# CONNECTEUR_1.net
KiCad netlist of a schematic drawn in Altium Designer
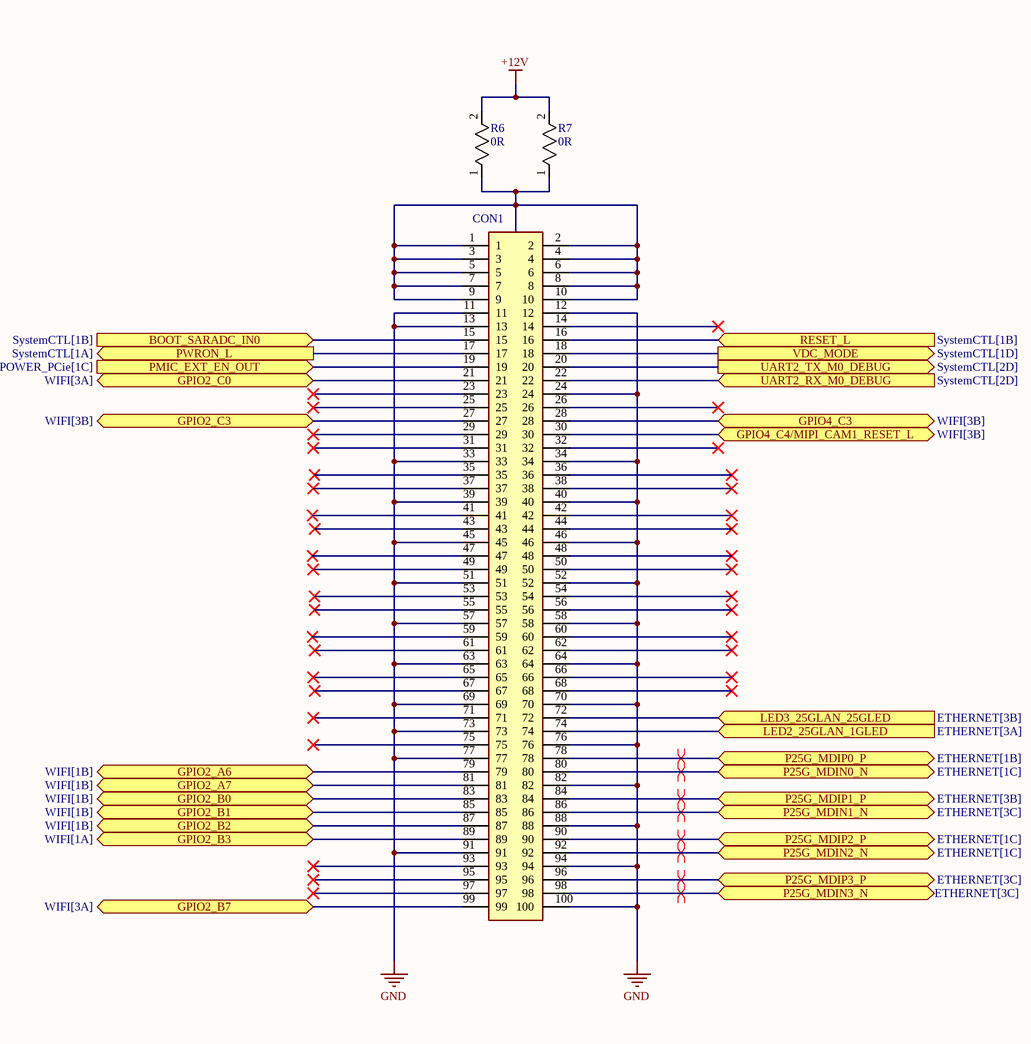
[diagram p0: CONNECTEUR_1.SchDoc, right]

(export (version "E")
  (design (tool "Eeschema 10.0.6"))
  (components
    (comp (ref "CON1")
      (value "DF40HC")
      (footprint "SamacSys:DF40HC30100DS04V51")
      (description "Stacking Board Connector, DF40 Series, Receptacle, 0.4 mm, 100, Surface Mount, G")
      (fields
        (field (name "MANUFACTURER_PART_NUMBER") "DF40HC(3.0)-100DS-0.4V(51")
        (field (name "MOUSER PART NUMBER") "798-DF40HC30100DS451")
      )
      (libsource (lib "SamacSys") (part "DF40HC(3.0)-100DS-0.4V(51)"))
    )
    (comp (ref "R6")
      (value "0R")
      (footprint "SamacSys:ERJ3EKF1000V")
      (description "Zero Ohm Resistor, Jumper, 0603 [1608 Metric], Thick Film, 100 mW, 1 A, Surface Mount")
      (fields
        (field (name "MANUFACTURER_PART_NUMBER") "ERJ-3GEY0R00V")
        (field (name "MOUSER PART NUMBER") "667-ERJ-3GEY0R00V")
      )
      (libsource (lib "SamacSys") (part "ERJ-3GEY0R00V"))
    )
    (comp (ref "R7")
      (value "0R")
      (footprint "SamacSys:ERJ3EKF1000V")
      (description "Zero Ohm Resistor, Jumper, 0603 [1608 Metric], Thick Film, 100 mW, 1 A, Surface Mount")
      (fields
        (field (name "MANUFACTURER_PART_NUMBER") "ERJ-3GEY0R00V")
        (field (name "MOUSER PART NUMBER") "667-ERJ-3GEY0R00V")
      )
      (libsource (lib "SamacSys") (part "ERJ-3GEY0R00V"))
    )
  )
  (nets
    (net (code "1") (name "+12V") (class "Default")
      (node (ref "R6") (pin "2") (pinfunction "2_2") (pintype "passive"))
      (node (ref "R7") (pin "2") (pinfunction "2_2") (pintype "passive"))
    )
    (net (code "2") (name "/BOOT_SARADC_IN0") (class "Default")
      (node (ref "CON1") (pin "15") (pinfunction "15_15") (pintype "passive"))
    )
    (net (code "3") (name "/GPIO2_A6") (class "Default")
      (node (ref "CON1") (pin "79") (pinfunction "79_79") (pintype "passive"))
    )
    (net (code "4") (name "/GPIO2_A7") (class "Default")
      (node (ref "CON1") (pin "81") (pinfunction "81_81") (pintype "passive"))
    )
    (net (code "5") (name "/GPIO2_B0") (class "Default")
      (node (ref "CON1") (pin "83") (pinfunction "83_83") (pintype "passive"))
    )
    (net (code "6") (name "/GPIO2_B1") (class "Default")
      (node (ref "CON1") (pin "85") (pinfunction "85_85") (pintype "passive"))
    )
    (net (code "7") (name "/GPIO2_B2") (class "Default")
      (node (ref "CON1") (pin "87") (pinfunction "87_87") (pintype "passive"))
    )
    (net (code "8") (name "/GPIO2_B3") (class "Default")
      (node (ref "CON1") (pin "89") (pinfunction "89_89") (pintype "passive"))
    )
    (net (code "9") (name "/GPIO2_B7") (class "Default")
      (node (ref "CON1") (pin "99") (pinfunction "99_99") (pintype "passive"))
    )
    (net (code "10") (name "/GPIO2_C0") (class "Default")
      (node (ref "CON1") (pin "21") (pinfunction "21_21") (pintype "passive"))
    )
    (net (code "11") (name "/GPIO2_C3") (class "Default")
      (node (ref "CON1") (pin "27") (pinfunction "27_27") (pintype "passive"))
    )
    (net (code "12") (name "/GPIO4_C3") (class "Default")
      (node (ref "CON1") (pin "28") (pinfunction "28_28") (pintype "passive"))
    )
    (net (code "13") (name "/GPIO4_C4{slash}MIPI_CAM1_RESET_L") (class "Default")
      (node (ref "CON1") (pin "30") (pinfunction "30_30") (pintype "passive"))
    )
    (net (code "14") (name "/LED2_25GLAN_1GLED") (class "Default")
      (node (ref "CON1") (pin "74") (pinfunction "74_74") (pintype "passive"))
    )
    (net (code "15") (name "/LED3_25GLAN_25GLED") (class "Default")
      (node (ref "CON1") (pin "72") (pinfunction "72_72") (pintype "passive"))
    )
    (net (code "16") (name "/P25G_MDIN0_N") (class "Default")
      (node (ref "CON1") (pin "80") (pinfunction "80_80") (pintype "passive"))
    )
    (net (code "17") (name "/P25G_MDIN1_N") (class "Default")
      (node (ref "CON1") (pin "86") (pinfunction "86_86") (pintype "passive"))
    )
    (net (code "18") (name "/P25G_MDIN2_N") (class "Default")
      (node (ref "CON1") (pin "92") (pinfunction "92_92") (pintype "passive"))
    )
    (net (code "19") (name "/P25G_MDIN3_N") (class "Default")
      (node (ref "CON1") (pin "98") (pinfunction "98_98") (pintype "passive"))
    )
    (net (code "20") (name "/P25G_MDIP0_P") (class "Default")
      (node (ref "CON1") (pin "78") (pinfunction "78_78") (pintype "passive"))
    )
    (net (code "21") (name "/P25G_MDIP1_P") (class "Default")
      (node (ref "CON1") (pin "84") (pinfunction "84_84") (pintype "passive"))
    )
    (net (code "22") (name "/P25G_MDIP2_P") (class "Default")
      (node (ref "CON1") (pin "90") (pinfunction "90_90") (pintype "passive"))
    )
    (net (code "23") (name "/P25G_MDIP3_P") (class "Default")
      (node (ref "CON1") (pin "96") (pinfunction "96_96") (pintype "passive"))
    )
    (net (code "24") (name "/PMIC_EXT_EN_OUT") (class "Default")
      (node (ref "CON1") (pin "19") (pinfunction "19_19") (pintype "passive"))
    )
    (net (code "25") (name "/PWRON_L") (class "Default")
      (node (ref "CON1") (pin "17") (pinfunction "17_17") (pintype "passive"))
    )
    (net (code "26") (name "/RESET_L") (class "Default")
      (node (ref "CON1") (pin "16") (pinfunction "16_16") (pintype "passive"))
    )
    (net (code "27") (name "/UART2_RX_M0_DEBUG") (class "Default")
      (node (ref "CON1") (pin "22") (pinfunction "22_22") (pintype "passive"))
    )
    (net (code "28") (name "/UART2_TX_M0_DEBUG") (class "Default")
      (node (ref "CON1") (pin "20") (pinfunction "20_20") (pintype "passive"))
    )
    (net (code "29") (name "/VDC_MODE") (class "Default")
      (node (ref "CON1") (pin "18") (pinfunction "18_18") (pintype "passive"))
    )
    (net (code "30") (name "GND") (class "Default")
      (node (ref "CON1") (pin "100") (pinfunction "100_100") (pintype "passive"))
      (node (ref "CON1") (pin "11") (pinfunction "11_11") (pintype "passive"))
      (node (ref "CON1") (pin "12") (pinfunction "12_12") (pintype "passive"))
      (node (ref "CON1") (pin "13") (pinfunction "13_13") (pintype "passive"))
      (node (ref "CON1") (pin "24") (pinfunction "24_24") (pintype "passive"))
      (node (ref "CON1") (pin "33") (pinfunction "33_33") (pintype "passive"))
      (node (ref "CON1") (pin "34") (pinfunction "34_34") (pintype "passive"))
      (node (ref "CON1") (pin "39") (pinfunction "39_39") (pintype "passive"))
      (node (ref "CON1") (pin "40") (pinfunction "40_40") (pintype "passive"))
      (node (ref "CON1") (pin "45") (pinfunction "45_45") (pintype "passive"))
      (node (ref "CON1") (pin "46") (pinfunction "46_46") (pintype "passive"))
      (node (ref "CON1") (pin "51") (pinfunction "51_51") (pintype "passive"))
      (node (ref "CON1") (pin "52") (pinfunction "52_52") (pintype "passive"))
      (node (ref "CON1") (pin "57") (pinfunction "57_57") (pintype "passive"))
      (node (ref "CON1") (pin "58") (pinfunction "58_58") (pintype "passive"))
      (node (ref "CON1") (pin "63") (pinfunction "63_63") (pintype "passive"))
      (node (ref "CON1") (pin "64") (pinfunction "64_64") (pintype "passive"))
      (node (ref "CON1") (pin "69") (pinfunction "69_69") (pintype "passive"))
      (node (ref "CON1") (pin "70") (pinfunction "70_70") (pintype "passive"))
      (node (ref "CON1") (pin "73") (pinfunction "73_73") (pintype "passive"))
      (node (ref "CON1") (pin "76") (pinfunction "76_76") (pintype "passive"))
      (node (ref "CON1") (pin "77") (pinfunction "77_77") (pintype "passive"))
      (node (ref "CON1") (pin "82") (pinfunction "82_82") (pintype "passive"))
      (node (ref "CON1") (pin "88") (pinfunction "88_88") (pintype "passive"))
      (node (ref "CON1") (pin "91") (pinfunction "91_91") (pintype "passive"))
      (node (ref "CON1") (pin "94") (pinfunction "94_94") (pintype "passive"))
    )
    (net (code "31") (name "Net-(CON1-Pad1)") (class "Default")
      (node (ref "CON1") (pin "1") (pinfunction "1_1") (pintype "passive"))
      (node (ref "CON1") (pin "10") (pinfunction "10_10") (pintype "passive"))
      (node (ref "CON1") (pin "2") (pinfunction "2_2") (pintype "passive"))
      (node (ref "CON1") (pin "3") (pinfunction "3_3") (pintype "passive"))
      (node (ref "CON1") (pin "4") (pinfunction "4_4") (pintype "passive"))
      (node (ref "CON1") (pin "5") (pinfunction "5_5") (pintype "passive"))
      (node (ref "CON1") (pin "6") (pinfunction "6_6") (pintype "passive"))
      (node (ref "CON1") (pin "7") (pinfunction "7_7") (pintype "passive"))
      (node (ref "CON1") (pin "8") (pinfunction "8_8") (pintype "passive"))
      (node (ref "CON1") (pin "9") (pinfunction "9_9") (pintype "passive"))
      (node (ref "R6") (pin "1") (pinfunction "1_1") (pintype "passive"))
      (node (ref "R7") (pin "1") (pinfunction "1_1") (pintype "passive"))
    )
    (net (code "32") (name "unconnected-(CON1-Pad14)") (class "Default")
      (node (ref "CON1") (pin "14") (pinfunction "14_14") (pintype "passive+no_connect"))
    )
    (net (code "33") (name "unconnected-(CON1-Pad23)") (class "Default")
      (node (ref "CON1") (pin "23") (pinfunction "23_23") (pintype "passive+no_connect"))
    )
    (net (code "34") (name "unconnected-(CON1-Pad25)") (class "Default")
      (node (ref "CON1") (pin "25") (pinfunction "25_25") (pintype "passive+no_connect"))
    )
    (net (code "35") (name "unconnected-(CON1-Pad26)") (class "Default")
      (node (ref "CON1") (pin "26") (pinfunction "26_26") (pintype "passive+no_connect"))
    )
    (net (code "36") (name "unconnected-(CON1-Pad29)") (class "Default")
      (node (ref "CON1") (pin "29") (pinfunction "29_29") (pintype "passive+no_connect"))
    )
    (net (code "37") (name "unconnected-(CON1-Pad31)") (class "Default")
      (node (ref "CON1") (pin "31") (pinfunction "31_31") (pintype "passive+no_connect"))
    )
    (net (code "38") (name "unconnected-(CON1-Pad32)") (class "Default")
      (node (ref "CON1") (pin "32") (pinfunction "32_32") (pintype "passive+no_connect"))
    )
    (net (code "39") (name "unconnected-(CON1-Pad35)") (class "Default")
      (node (ref "CON1") (pin "35") (pinfunction "35_35") (pintype "passive+no_connect"))
    )
    (net (code "40") (name "unconnected-(CON1-Pad36)") (class "Default")
      (node (ref "CON1") (pin "36") (pinfunction "36_36") (pintype "passive+no_connect"))
    )
    (net (code "41") (name "unconnected-(CON1-Pad37)") (class "Default")
      (node (ref "CON1") (pin "37") (pinfunction "37_37") (pintype "passive+no_connect"))
    )
    (net (code "42") (name "unconnected-(CON1-Pad38)") (class "Default")
      (node (ref "CON1") (pin "38") (pinfunction "38_38") (pintype "passive+no_connect"))
    )
    (net (code "43") (name "unconnected-(CON1-Pad41)") (class "Default")
      (node (ref "CON1") (pin "41") (pinfunction "41_41") (pintype "passive+no_connect"))
    )
    (net (code "44") (name "unconnected-(CON1-Pad42)") (class "Default")
      (node (ref "CON1") (pin "42") (pinfunction "42_42") (pintype "passive+no_connect"))
    )
    (net (code "45") (name "unconnected-(CON1-Pad43)") (class "Default")
      (node (ref "CON1") (pin "43") (pinfunction "43_43") (pintype "passive+no_connect"))
    )
    (net (code "46") (name "unconnected-(CON1-Pad44)") (class "Default")
      (node (ref "CON1") (pin "44") (pinfunction "44_44") (pintype "passive+no_connect"))
    )
    (net (code "47") (name "unconnected-(CON1-Pad47)") (class "Default")
      (node (ref "CON1") (pin "47") (pinfunction "47_47") (pintype "passive+no_connect"))
    )
    (net (code "48") (name "unconnected-(CON1-Pad48)") (class "Default")
      (node (ref "CON1") (pin "48") (pinfunction "48_48") (pintype "passive+no_connect"))
    )
    (net (code "49") (name "unconnected-(CON1-Pad49)") (class "Default")
      (node (ref "CON1") (pin "49") (pinfunction "49_49") (pintype "passive+no_connect"))
    )
    (net (code "50") (name "unconnected-(CON1-Pad50)") (class "Default")
      (node (ref "CON1") (pin "50") (pinfunction "50_50") (pintype "passive+no_connect"))
    )
    (net (code "51") (name "unconnected-(CON1-Pad53)") (class "Default")
      (node (ref "CON1") (pin "53") (pinfunction "53_53") (pintype "passive+no_connect"))
    )
    (net (code "52") (name "unconnected-(CON1-Pad54)") (class "Default")
      (node (ref "CON1") (pin "54") (pinfunction "54_54") (pintype "passive+no_connect"))
    )
    (net (code "53") (name "unconnected-(CON1-Pad55)") (class "Default")
      (node (ref "CON1") (pin "55") (pinfunction "55_55") (pintype "passive+no_connect"))
    )
    (net (code "54") (name "unconnected-(CON1-Pad56)") (class "Default")
      (node (ref "CON1") (pin "56") (pinfunction "56_56") (pintype "passive+no_connect"))
    )
    (net (code "55") (name "unconnected-(CON1-Pad59)") (class "Default")
      (node (ref "CON1") (pin "59") (pinfunction "59_59") (pintype "passive+no_connect"))
    )
    (net (code "56") (name "unconnected-(CON1-Pad60)") (class "Default")
      (node (ref "CON1") (pin "60") (pinfunction "60_60") (pintype "passive+no_connect"))
    )
    (net (code "57") (name "unconnected-(CON1-Pad61)") (class "Default")
      (node (ref "CON1") (pin "61") (pinfunction "61_61") (pintype "passive+no_connect"))
    )
    (net (code "58") (name "unconnected-(CON1-Pad62)") (class "Default")
      (node (ref "CON1") (pin "62") (pinfunction "62_62") (pintype "passive+no_connect"))
    )
    (net (code "59") (name "unconnected-(CON1-Pad65)") (class "Default")
      (node (ref "CON1") (pin "65") (pinfunction "65_65") (pintype "passive+no_connect"))
    )
    (net (code "60") (name "unconnected-(CON1-Pad66)") (class "Default")
      (node (ref "CON1") (pin "66") (pinfunction "66_66") (pintype "passive+no_connect"))
    )
    (net (code "61") (name "unconnected-(CON1-Pad67)") (class "Default")
      (node (ref "CON1") (pin "67") (pinfunction "67_67") (pintype "passive+no_connect"))
    )
    (net (code "62") (name "unconnected-(CON1-Pad68)") (class "Default")
      (node (ref "CON1") (pin "68") (pinfunction "68_68") (pintype "passive+no_connect"))
    )
    (net (code "63") (name "unconnected-(CON1-Pad71)") (class "Default")
      (node (ref "CON1") (pin "71") (pinfunction "71_71") (pintype "passive+no_connect"))
    )
    (net (code "64") (name "unconnected-(CON1-Pad75)") (class "Default")
      (node (ref "CON1") (pin "75") (pinfunction "75_75") (pintype "passive+no_connect"))
    )
    (net (code "65") (name "unconnected-(CON1-Pad93)") (class "Default")
      (node (ref "CON1") (pin "93") (pinfunction "93_93") (pintype "passive+no_connect"))
    )
    (net (code "66") (name "unconnected-(CON1-Pad95)") (class "Default")
      (node (ref "CON1") (pin "95") (pinfunction "95_95") (pintype "passive+no_connect"))
    )
    (net (code "67") (name "unconnected-(CON1-Pad97)") (class "Default")
      (node (ref "CON1") (pin "97") (pinfunction "97_97") (pintype "passive+no_connect"))
    )
  )
)
